# Base_Station.net
KiCad netlist of a schematic drawn in EAGLE
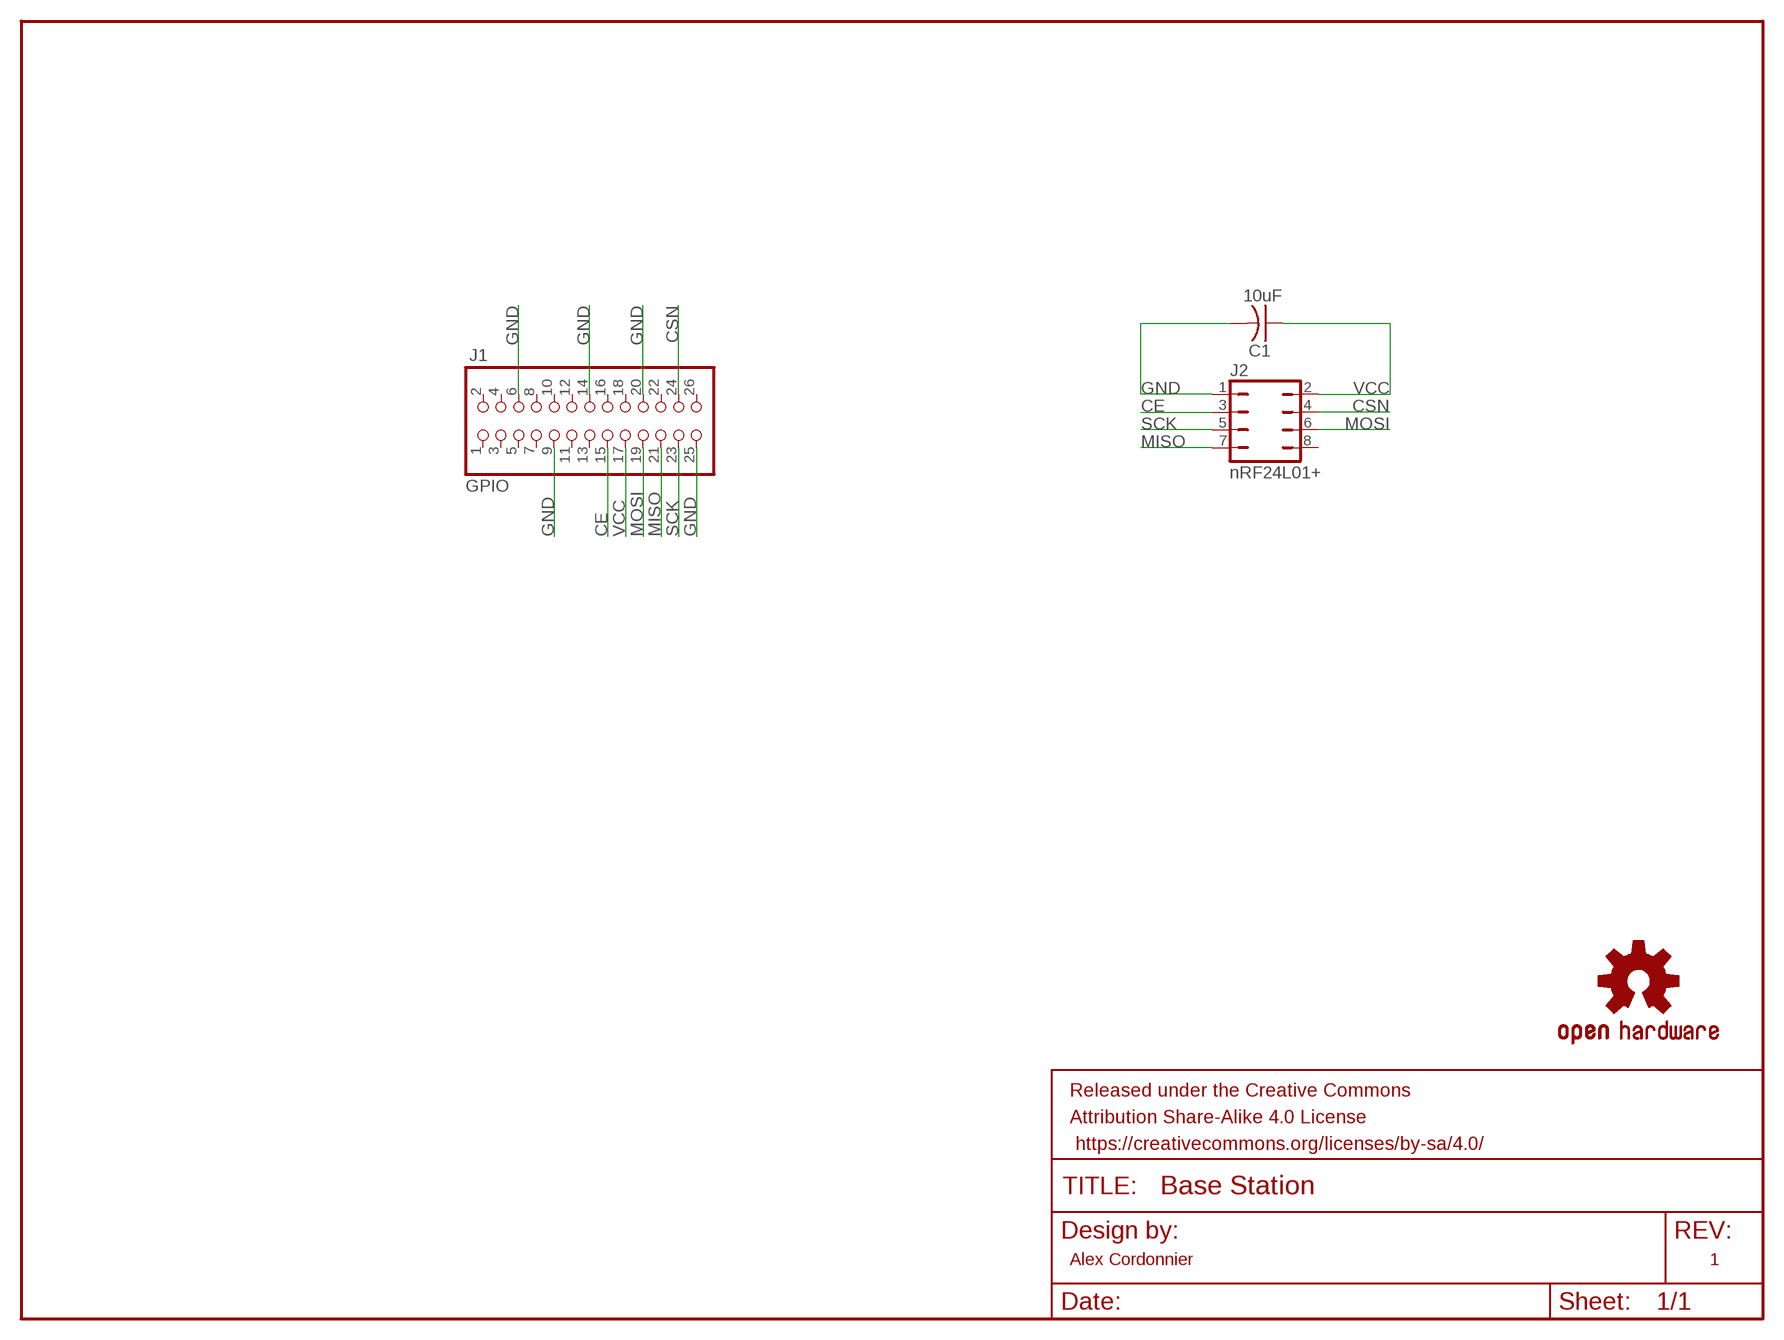
[diagram p0: schematic, sheet 1]

(export (version "E")
  (design (tool "Eeschema 10.0.6"))
  (components
    (comp (ref "C1")
      (value "10uF")
      (footprint "eagle-import:C1206K")
      (libsource (lib "eagle-import") (part "C-USC1206K"))
    )
    (comp (ref "FRAME1")
      (value "FRAME-LETTERNO_PACKAGE")
      (footprint "eagle-import:DUMMY")
      (fields (field (name "DESIGNER") "Nobody"))
      (libsource (lib "eagle-import") (part "FRAME-LETTERNO_PACKAGE"))
    )
    (comp (ref "J1")
      (value "GPIO")
      (footprint "eagle-import:2X13")
      (libsource (lib "eagle-import") (part "PINHD-2X13"))
    )
    (comp (ref "J2")
      (value "nRF24L01+")
      (footprint "eagle-import:FEMALE-2X4-SMT")
      (libsource (lib "eagle-import") (part "FEMALE-2X4-SMT"))
    )
    (comp (ref "LOGO1")
      (value "OSHW-LOGOS")
      (footprint "eagle-import:OSHW-LOGO-S")
      (libsource (lib "eagle-import") (part "OSHW-LOGOS"))
    )
  )
  (nets
    (net (code "1") (name "/CE") (class "Default")
      (node (ref "J1") (pin "15") (pinfunction "15_15") (pintype "passive"))
      (node (ref "J2") (pin "3") (pinfunction "3_3") (pintype "passive"))
    )
    (net (code "2") (name "/CSN") (class "Default")
      (node (ref "J1") (pin "24") (pinfunction "24_24") (pintype "passive"))
      (node (ref "J2") (pin "4") (pinfunction "4_4") (pintype "passive"))
    )
    (net (code "3") (name "/GND") (class "Default")
      (node (ref "C1") (pin "2") (pinfunction "2_2") (pintype "passive"))
      (node (ref "J1") (pin "14") (pinfunction "14_14") (pintype "passive"))
      (node (ref "J1") (pin "20") (pinfunction "20_20") (pintype "passive"))
      (node (ref "J1") (pin "25") (pinfunction "25_25") (pintype "passive"))
      (node (ref "J1") (pin "6") (pinfunction "6_6") (pintype "passive"))
      (node (ref "J1") (pin "9") (pinfunction "9_9") (pintype "passive"))
      (node (ref "J2") (pin "1") (pinfunction "1_1") (pintype "passive"))
    )
    (net (code "4") (name "/MISO") (class "Default")
      (node (ref "J1") (pin "21") (pinfunction "21_21") (pintype "passive"))
      (node (ref "J2") (pin "7") (pinfunction "7_7") (pintype "passive"))
    )
    (net (code "5") (name "/MOSI") (class "Default")
      (node (ref "J1") (pin "19") (pinfunction "19_19") (pintype "passive"))
      (node (ref "J2") (pin "6") (pinfunction "6_6") (pintype "passive"))
    )
    (net (code "6") (name "/SCK") (class "Default")
      (node (ref "J1") (pin "23") (pinfunction "23_23") (pintype "passive"))
      (node (ref "J2") (pin "5") (pinfunction "5_5") (pintype "passive"))
    )
    (net (code "7") (name "/VCC") (class "Default")
      (node (ref "C1") (pin "1") (pinfunction "1_1") (pintype "passive"))
      (node (ref "J1") (pin "17") (pinfunction "17_17") (pintype "passive"))
      (node (ref "J2") (pin "2") (pinfunction "2_2") (pintype "passive"))
    )
    (net (code "8") (name "unconnected-(J1-Pad1)") (class "Default")
      (node (ref "J1") (pin "1") (pinfunction "1_1") (pintype "passive"))
    )
    (net (code "9") (name "unconnected-(J1-Pad2)") (class "Default")
      (node (ref "J1") (pin "2") (pinfunction "2_2") (pintype "passive"))
    )
    (net (code "10") (name "unconnected-(J1-Pad3)") (class "Default")
      (node (ref "J1") (pin "3") (pinfunction "3_3") (pintype "passive"))
    )
    (net (code "11") (name "unconnected-(J1-Pad4)") (class "Default")
      (node (ref "J1") (pin "4") (pinfunction "4_4") (pintype "passive"))
    )
    (net (code "12") (name "unconnected-(J1-Pad5)") (class "Default")
      (node (ref "J1") (pin "5") (pinfunction "5_5") (pintype "passive"))
    )
    (net (code "13") (name "unconnected-(J1-Pad7)") (class "Default")
      (node (ref "J1") (pin "7") (pinfunction "7_7") (pintype "passive"))
    )
    (net (code "14") (name "unconnected-(J1-Pad8)") (class "Default")
      (node (ref "J1") (pin "8") (pinfunction "8_8") (pintype "passive"))
    )
    (net (code "15") (name "unconnected-(J1-Pad10)") (class "Default")
      (node (ref "J1") (pin "10") (pinfunction "10_10") (pintype "passive"))
    )
    (net (code "16") (name "unconnected-(J1-Pad11)") (class "Default")
      (node (ref "J1") (pin "11") (pinfunction "11_11") (pintype "passive"))
    )
    (net (code "17") (name "unconnected-(J1-Pad12)") (class "Default")
      (node (ref "J1") (pin "12") (pinfunction "12_12") (pintype "passive"))
    )
    (net (code "18") (name "unconnected-(J1-Pad13)") (class "Default")
      (node (ref "J1") (pin "13") (pinfunction "13_13") (pintype "passive"))
    )
    (net (code "19") (name "unconnected-(J1-Pad16)") (class "Default")
      (node (ref "J1") (pin "16") (pinfunction "16_16") (pintype "passive"))
    )
    (net (code "20") (name "unconnected-(J1-Pad18)") (class "Default")
      (node (ref "J1") (pin "18") (pinfunction "18_18") (pintype "passive"))
    )
    (net (code "21") (name "unconnected-(J1-Pad22)") (class "Default")
      (node (ref "J1") (pin "22") (pinfunction "22_22") (pintype "passive"))
    )
    (net (code "22") (name "unconnected-(J1-Pad26)") (class "Default")
      (node (ref "J1") (pin "26") (pinfunction "26_26") (pintype "passive"))
    )
    (net (code "23") (name "unconnected-(J2-Pad8)") (class "Default")
      (node (ref "J2") (pin "8") (pinfunction "8_8") (pintype "passive"))
    )
  )
)
